# ECU_AutoRC_PWR_SUPPLY_6A_r00.net
KiCad netlist of a schematic drawn in Altium Designer
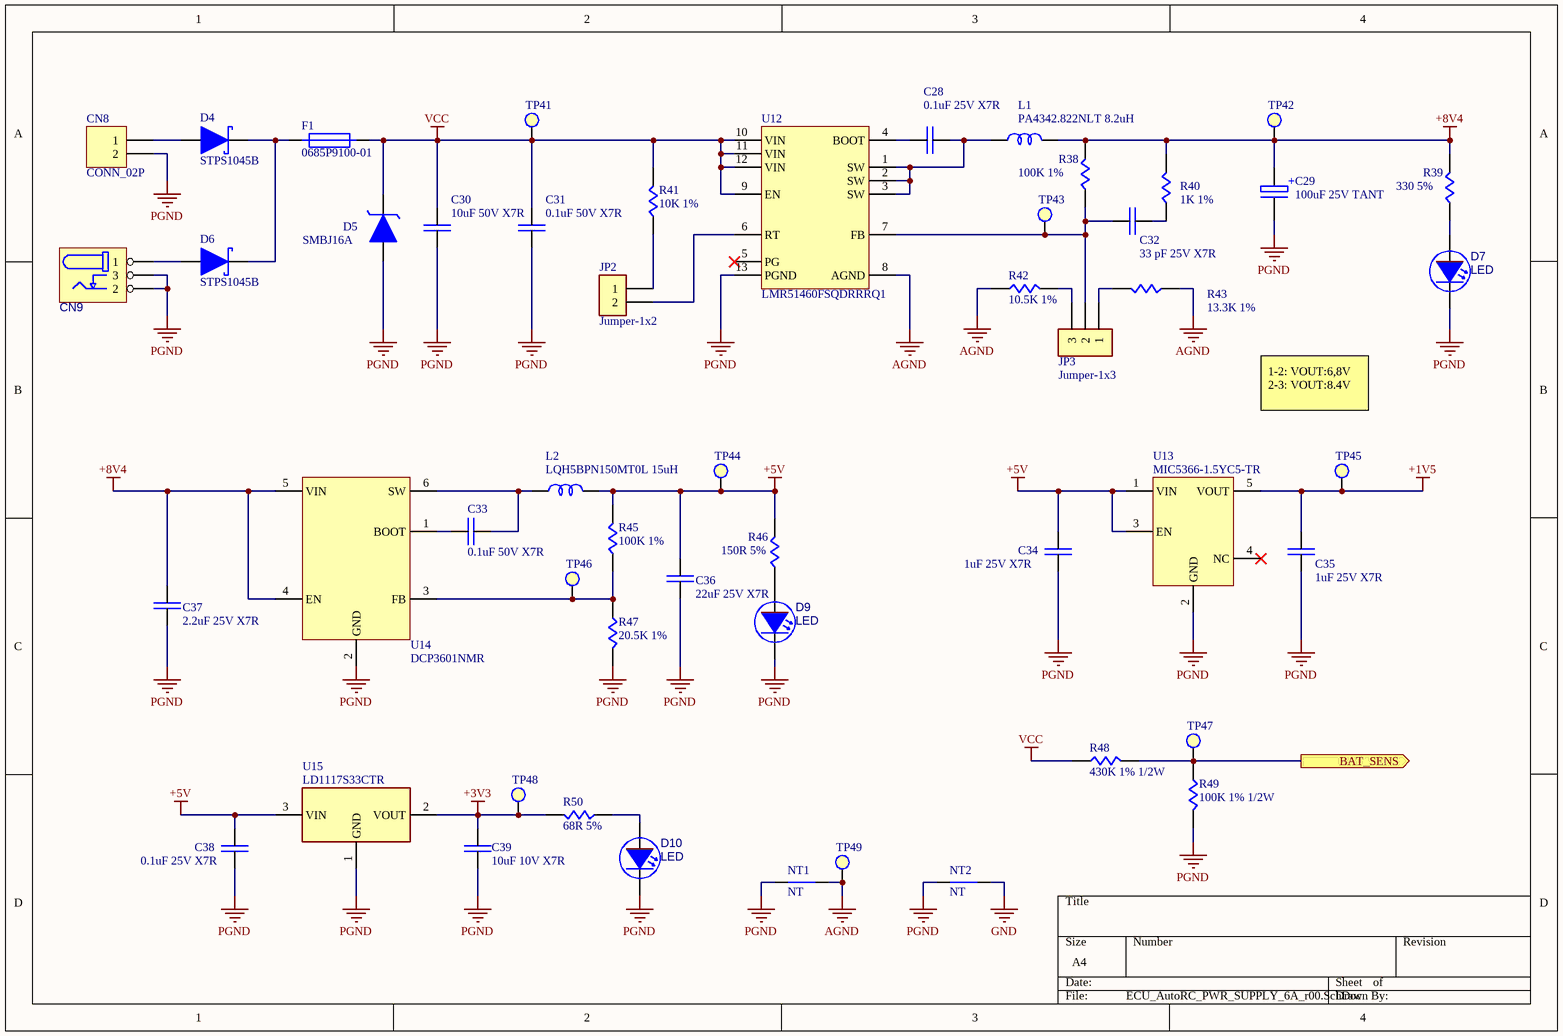
[diagram p0: ECU_AutoRC_PWR_SUPPLY_6A_r00.SchDoc]

(export (version "E")
  (design (tool "Eeschema 10.0.6"))
  (components
    (comp (ref "C28")
      (value "0.1uF 25V X7R")
      (footprint "C_0805")
      (description "Non Polarizated Capacitor")
      (libsource (lib "ECU_AutoRC_r00") (part "Capacitor NP"))
    )
    (comp (ref "C29")
      (value "100uF 25V TANT")
      (footprint "C_TANT_2917")
      (description "Polarizated Capacitor")
      (libsource (lib "ECU_AutoRC_r00") (part "Capacitor Polarizado"))
    )
    (comp (ref "C30")
      (value "10uF 50V X7R")
      (footprint "C_1206")
      (description "Non Polarizated Capacitor")
      (libsource (lib "ECU_AutoRC_r00") (part "Capacitor NP"))
    )
    (comp (ref "C31")
      (value "0.1uF 50V X7R")
      (footprint "C_0805")
      (description "Non Polarizated Capacitor")
      (libsource (lib "ECU_AutoRC_r00") (part "Capacitor NP"))
    )
    (comp (ref "C32")
      (value "33 pF 25V X7R")
      (footprint "C_0805")
      (description "Non Polarizated Capacitor")
      (libsource (lib "ECU_AutoRC_r00") (part "Capacitor NP"))
    )
    (comp (ref "C33")
      (value "0.1uF 50V X7R")
      (footprint "C_0805")
      (description "Non Polarizated Capacitor")
      (libsource (lib "ECU_AutoRC_r00") (part "Capacitor NP"))
    )
    (comp (ref "C34")
      (value "1uF 25V X7R")
      (footprint "C_0805")
      (description "Non Polarizated Capacitor")
      (libsource (lib "ECU_AutoRC_r00") (part "Capacitor NP"))
    )
    (comp (ref "C35")
      (value "1uF 25V X7R")
      (footprint "C_0805")
      (description "Non Polarizated Capacitor")
      (libsource (lib "ECU_AutoRC_r00") (part "Capacitor NP"))
    )
    (comp (ref "C36")
      (value "22uF 25V X7R")
      (footprint "C_0805")
      (description "Non Polarizated Capacitor")
      (libsource (lib "ECU_AutoRC_r00") (part "Capacitor NP"))
    )
    (comp (ref "C37")
      (value "2.2uF 25V X7R")
      (footprint "C_0805")
      (description "Non Polarizated Capacitor")
      (libsource (lib "ECU_AutoRC_r00") (part "Capacitor NP"))
    )
    (comp (ref "C38")
      (value "0.1uF 25V X7R")
      (footprint "C_0805")
      (description "Non Polarizated Capacitor")
      (libsource (lib "ECU_AutoRC_r00") (part "Capacitor NP"))
    )
    (comp (ref "C39")
      (value "10uF 10V X7R")
      (footprint "C_0805")
      (description "Non Polarizated Capacitor")
      (libsource (lib "ECU_AutoRC_r00") (part "Capacitor NP"))
    )
    (comp (ref "CN8")
      (value "CONN_02P")
      (footprint "CONN_BAT")
      (description "2 Pin Connector")
      (libsource (lib "ECU_AutoRC_r00") (part "CONN_02P"))
    )
    (comp (ref "CN9")
      (value "CN_PowerJack")
      (footprint "PJ002B")
      (description "Barrel Power Connector")
      (libsource (lib "ECU_AutoRC_r00") (part "CN_PowerJack"))
    )
    (comp (ref "D4")
      (value "STPS1045B")
      (footprint "TO252_1")
      (description "Diode Schottky")
      (libsource (lib "ECU_AutoRC_r00") (part "Diode_Schottky"))
    )
    (comp (ref "D5")
      (value "SMBJ16A")
      (footprint "D_SMB")
      (description "Diode Zener")
      (libsource (lib "ECU_AutoRC_r00") (part "Diode_Zener"))
    )
    (comp (ref "D6")
      (value "STPS1045B")
      (footprint "TO252_1")
      (description "Diode Schottky")
      (libsource (lib "ECU_AutoRC_r00") (part "Diode_Schottky"))
    )
    (comp (ref "D7") (value "LED") (footprint "LED_0805") (libsource (lib "ECU_AutoRC_r00") (part "LED")))
    (comp (ref "D9") (value "LED") (footprint "LED_0805") (libsource (lib "ECU_AutoRC_r00") (part "LED")))
    (comp (ref "D10") (value "LED") (footprint "LED_0805") (libsource (lib "ECU_AutoRC_r00") (part "LED")))
    (comp (ref "F1")
      (value "0685P9100-01")
      (footprint "F_1206")
      (description "Fuse ¦ Quick Acting")
      (fields (field (name "MF") "Bel Fuse") (field (name "MP") "0679L1000-05"))
      (libsource (lib "ECU_AutoRC_r00") (part "FUSE"))
    )
    (comp (ref "JP2")
      (value "Jumper-1x2")
      (footprint "Header_M_1x2_0.1\"")
      (libsource (lib "ECU_AutoRC_r00") (part "Jumper-1x2"))
    )
    (comp (ref "JP3")
      (value "Jumper-1x3")
      (footprint "Header_M_1x3_0.1\"")
      (libsource (lib "ECU_AutoRC_r00") (part "Jumper-1x3"))
    )
    (comp (ref "L1")
      (value "PA4342.822NLT 8.2uH")
      (footprint "IND_PA4342.822NLT")
      (description "Inductor")
      (libsource (lib "ECU_AutoRC_r00") (part "Inductor"))
    )
    (comp (ref "L2")
      (value "LQH5BPN150MT0L 15uH")
      (footprint "IND_LQH5BPN150MT0L")
      (description "Inductor")
      (libsource (lib "ECU_AutoRC_r00") (part "Inductor"))
    )
    (comp (ref "NT1")
      (value "NT")
      (footprint "NET_TIE")
      (libsource (lib "ECU_AutoRC_r00") (part "NET_TIE_SMD"))
    )
    (comp (ref "NT2")
      (value "NT")
      (footprint "NET_TIE")
      (libsource (lib "ECU_AutoRC_r00") (part "NET_TIE_SMD"))
    )
    (comp (ref "R38")
      (value "100K 1%")
      (footprint "R_0805")
      (description "Resistor")
      (libsource (lib "ECU_AutoRC_r00") (part "Resistor"))
    )
    (comp (ref "R39")
      (value "330 5%")
      (footprint "R_0805")
      (description "Resistor")
      (libsource (lib "ECU_AutoRC_r00") (part "Resistor"))
    )
    (comp (ref "R40")
      (value "1K 1%")
      (footprint "R_0805")
      (description "Resistor")
      (libsource (lib "ECU_AutoRC_r00") (part "Resistor"))
    )
    (comp (ref "R41")
      (value "10K 1%")
      (footprint "R_0805")
      (description "Resistor")
      (libsource (lib "ECU_AutoRC_r00") (part "Resistor"))
    )
    (comp (ref "R42")
      (value "10.5K 1%")
      (footprint "R_0805")
      (description "Resistor")
      (libsource (lib "ECU_AutoRC_r00") (part "Resistor"))
    )
    (comp (ref "R43")
      (value "13.3K 1%")
      (footprint "R_0805")
      (description "Resistor")
      (libsource (lib "ECU_AutoRC_r00") (part "Resistor"))
    )
    (comp (ref "R45")
      (value "100K 1%")
      (footprint "R_0805")
      (description "Resistor")
      (libsource (lib "ECU_AutoRC_r00") (part "Resistor"))
    )
    (comp (ref "R46")
      (value "150R 5%")
      (footprint "R_0805")
      (description "Resistor")
      (libsource (lib "ECU_AutoRC_r00") (part "Resistor"))
    )
    (comp (ref "R47")
      (value "20.5K 1%")
      (footprint "R_0805")
      (description "Resistor")
      (libsource (lib "ECU_AutoRC_r00") (part "Resistor"))
    )
    (comp (ref "R48")
      (value "430K 1% 1/2W")
      (footprint "R_1210")
      (description "Resistor")
      (libsource (lib "ECU_AutoRC_r00") (part "Resistor"))
    )
    (comp (ref "R49")
      (value "100K 1% 1/2W")
      (footprint "R_1210")
      (description "Resistor")
      (libsource (lib "ECU_AutoRC_r00") (part "Resistor"))
    )
    (comp (ref "R50")
      (value "68R 5%")
      (footprint "R_0805")
      (description "Resistor")
      (libsource (lib "ECU_AutoRC_r00") (part "Resistor"))
    )
    (comp (ref "TP41")
      (value "Test Point")
      (footprint "TEST_POINT")
      (libsource (lib "ECU_AutoRC_r00") (part "TestPoint"))
    )
    (comp (ref "TP42")
      (value "Test Point")
      (footprint "TEST_POINT")
      (libsource (lib "ECU_AutoRC_r00") (part "TestPoint"))
    )
    (comp (ref "TP43")
      (value "Test Point")
      (footprint "TEST_POINT")
      (libsource (lib "ECU_AutoRC_r00") (part "TestPoint"))
    )
    (comp (ref "TP44")
      (value "Test Point")
      (footprint "TEST_POINT")
      (libsource (lib "ECU_AutoRC_r00") (part "TestPoint"))
    )
    (comp (ref "TP45")
      (value "Test Point")
      (footprint "TEST_POINT")
      (libsource (lib "ECU_AutoRC_r00") (part "TestPoint"))
    )
    (comp (ref "TP46")
      (value "Test Point")
      (footprint "TEST_POINT")
      (libsource (lib "ECU_AutoRC_r00") (part "TestPoint"))
    )
    (comp (ref "TP47")
      (value "Test Point")
      (footprint "TEST_POINT")
      (libsource (lib "ECU_AutoRC_r00") (part "TestPoint"))
    )
    (comp (ref "TP48")
      (value "Test Point")
      (footprint "TEST_POINT")
      (libsource (lib "ECU_AutoRC_r00") (part "TestPoint"))
    )
    (comp (ref "TP49")
      (value "Test Point")
      (footprint "TEST_POINT")
      (libsource (lib "ECU_AutoRC_r00") (part "TestPoint"))
    )
    (comp (ref "U12")
      (value "LMR51460FSQDRRRQ1")
      (footprint "LMR51460FSQDRRRQ1")
      (description "IC REG BUCK ADJ 6A 12WSON")
      (libsource (lib "ECU_AutoRC_r00") (part "LMR51460FSQDRRRQ1"))
    )
    (comp (ref "U13")
      (value "MIC5366-1.5YC5-TR")
      (footprint "SC 70-5")
      (description "IC REG LINEAR 1.5V 150MA SC-70-5")
      (libsource (lib "ECU_AutoRC_r00") (part "MIC5366-1.5YC5-TR"))
    )
    (comp (ref "U14")
      (value "DCP3601NMR")
      (footprint "SOT23-6")
      (libsource (lib "ECU_AutoRC_r00") (part "DCP3601NMR"))
    )
    (comp (ref "U15")
      (value "LD1117S33CTR")
      (footprint "SOT-223")
      (description "IC REG LINEAR 3.3V 800MA SOT-223")
      (libsource (lib "ECU_AutoRC_r00") (part "LD1117S33CTR"))
    )
  )
  (nets
    (net (code "1") (name "+1V5") (class "Default")
      (node (ref "C35") (pin "1") (pinfunction "1_1") (pintype "passive"))
      (node (ref "TP45") (pin "1") (pintype "passive"))
      (node (ref "U13") (pin "5") (pinfunction "VOUT_5") (pintype "passive"))
    )
    (net (code "2") (name "+3V3") (class "Default")
      (node (ref "C39") (pin "1") (pinfunction "1_1") (pintype "passive"))
      (node (ref "R50") (pin "2") (pinfunction "2_2") (pintype "passive"))
      (node (ref "TP48") (pin "1") (pintype "passive"))
      (node (ref "U15") (pin "2") (pinfunction "VOUT_2") (pintype "passive"))
    )
    (net (code "3") (name "+5V") (class "Default")
      (node (ref "C34") (pin "1") (pinfunction "1_1") (pintype "passive"))
      (node (ref "C36") (pin "1") (pinfunction "1_1") (pintype "passive"))
      (node (ref "C38") (pin "1") (pinfunction "1_1") (pintype "passive"))
      (node (ref "L2") (pin "2") (pinfunction "2_2") (pintype "passive"))
      (node (ref "R45") (pin "2") (pinfunction "2_2") (pintype "passive"))
      (node (ref "R46") (pin "2") (pinfunction "2_2") (pintype "passive"))
      (node (ref "TP44") (pin "1") (pintype "passive"))
      (node (ref "U13") (pin "1") (pinfunction "VIN_1") (pintype "passive"))
      (node (ref "U13") (pin "3") (pinfunction "EN_3") (pintype "passive"))
      (node (ref "U15") (pin "3") (pinfunction "VIN_3") (pintype "passive"))
    )
    (net (code "4") (name "+8V4") (class "Default")
      (node (ref "C29") (pin "1") (pinfunction "1_1") (pintype "passive"))
      (node (ref "C37") (pin "1") (pinfunction "1_1") (pintype "passive"))
      (node (ref "L1") (pin "2") (pinfunction "2_2") (pintype "passive"))
      (node (ref "R38") (pin "2") (pinfunction "2_2") (pintype "passive"))
      (node (ref "R39") (pin "2") (pinfunction "2_2") (pintype "passive"))
      (node (ref "R40") (pin "2") (pinfunction "2_2") (pintype "passive"))
      (node (ref "TP42") (pin "1") (pintype "passive"))
      (node (ref "U14") (pin "4") (pinfunction "EN_4") (pintype "passive"))
      (node (ref "U14") (pin "5") (pinfunction "VIN_5") (pintype "passive"))
    )
    (net (code "5") (name "/BAT_SENS") (class "Default")
      (node (ref "R48") (pin "2") (pinfunction "2_2") (pintype "passive"))
      (node (ref "R49") (pin "1") (pinfunction "1_1") (pintype "passive"))
      (node (ref "TP47") (pin "1") (pintype "passive"))
    )
    (net (code "6") (name "AGND") (class "Default")
      (node (ref "NT1") (pin "2") (pinfunction "2_2") (pintype "passive"))
      (node (ref "R42") (pin "1") (pinfunction "1_1") (pintype "passive"))
      (node (ref "R43") (pin "1") (pinfunction "1_1") (pintype "passive"))
      (node (ref "TP49") (pin "1") (pintype "passive"))
      (node (ref "U12") (pin "8") (pinfunction "AGND_8") (pintype "passive"))
    )
    (net (code "7") (name "GND") (class "Default")
      (node (ref "NT2") (pin "2") (pinfunction "2_2") (pintype "passive"))
    )
    (net (code "8") (name "Net-(C28-Pad2)") (class "Default")
      (node (ref "C28") (pin "2") (pinfunction "2_2") (pintype "passive"))
      (node (ref "L1") (pin "1") (pinfunction "1_1") (pintype "passive"))
      (node (ref "U12") (pin "1") (pinfunction "SW_1") (pintype "passive"))
      (node (ref "U12") (pin "2") (pinfunction "SW_2") (pintype "passive"))
      (node (ref "U12") (pin "3") (pinfunction "SW_3") (pintype "passive"))
    )
    (net (code "9") (name "Net-(C32-Pad2)") (class "Default")
      (node (ref "C32") (pin "2") (pinfunction "2_2") (pintype "passive"))
      (node (ref "R40") (pin "1") (pinfunction "1_1") (pintype "passive"))
    )
    (net (code "10") (name "Net-(D4-Anode)") (class "Default")
      (node (ref "CN8") (pin "1") (pinfunction "1_1") (pintype "passive"))
      (node (ref "D4") (pin "1") (pinfunction "Anode_1") (pintype "passive"))
    )
    (net (code "11") (name "Net-(D4-Catode)") (class "Default")
      (node (ref "D4") (pin "2") (pinfunction "Catode_2") (pintype "passive"))
      (node (ref "D6") (pin "2") (pinfunction "Catode_2") (pintype "passive"))
      (node (ref "F1") (pin "1") (pinfunction "1_1") (pintype "passive"))
    )
    (net (code "12") (name "Net-(D6-Anode)") (class "Default")
      (node (ref "CN9") (pin "1") (pinfunction "1_1") (pintype "passive"))
      (node (ref "D6") (pin "1") (pinfunction "Anode_1") (pintype "passive"))
    )
    (net (code "13") (name "Net-(D7-A)") (class "Default")
      (node (ref "D7") (pin "1") (pinfunction "A_1") (pintype "passive"))
      (node (ref "R39") (pin "1") (pinfunction "1_1") (pintype "passive"))
    )
    (net (code "14") (name "Net-(D9-A)") (class "Default")
      (node (ref "D9") (pin "1") (pinfunction "A_1") (pintype "passive"))
      (node (ref "R46") (pin "1") (pinfunction "1_1") (pintype "passive"))
    )
    (net (code "15") (name "Net-(D10-A)") (class "Default")
      (node (ref "D10") (pin "1") (pinfunction "A_1") (pintype "passive"))
      (node (ref "R50") (pin "1") (pinfunction "1_1") (pintype "passive"))
    )
    (net (code "16") (name "Net-(JP2-Pad1)") (class "Default")
      (node (ref "JP2") (pin "1") (pinfunction "1_1") (pintype "passive"))
      (node (ref "R41") (pin "1") (pinfunction "1_1") (pintype "passive"))
    )
    (net (code "17") (name "Net-(JP3-Pad1)") (class "Default")
      (node (ref "JP3") (pin "1") (pinfunction "1_1") (pintype "passive"))
      (node (ref "R43") (pin "2") (pinfunction "2_2") (pintype "passive"))
    )
    (net (code "18") (name "Net-(JP3-Pad3)") (class "Default")
      (node (ref "JP3") (pin "3") (pinfunction "3_3") (pintype "passive"))
      (node (ref "R42") (pin "2") (pinfunction "2_2") (pintype "passive"))
    )
    (net (code "19") (name "Net-(U12-BOOT)") (class "Default")
      (node (ref "C28") (pin "1") (pinfunction "1_1") (pintype "passive"))
      (node (ref "U12") (pin "4") (pinfunction "BOOT_4") (pintype "passive"))
    )
    (net (code "20") (name "Net-(U12-FB)") (class "Default")
      (node (ref "C32") (pin "1") (pinfunction "1_1") (pintype "passive"))
      (node (ref "JP3") (pin "2") (pinfunction "2_2") (pintype "passive"))
      (node (ref "R38") (pin "1") (pinfunction "1_1") (pintype "passive"))
      (node (ref "TP43") (pin "1") (pintype "passive"))
      (node (ref "U12") (pin "7") (pinfunction "FB_7") (pintype "passive"))
    )
    (net (code "21") (name "Net-(U12-RT)") (class "Default")
      (node (ref "JP2") (pin "2") (pinfunction "2_2") (pintype "passive"))
      (node (ref "U12") (pin "6") (pinfunction "RT_6") (pintype "passive"))
    )
    (net (code "22") (name "Net-(U14-BOOT)") (class "Default")
      (node (ref "C33") (pin "1") (pinfunction "1_1") (pintype "passive"))
      (node (ref "U14") (pin "1") (pinfunction "BOOT_1") (pintype "passive"))
    )
    (net (code "23") (name "Net-(U14-FB)") (class "Default")
      (node (ref "R45") (pin "1") (pinfunction "1_1") (pintype "passive"))
      (node (ref "R47") (pin "1") (pinfunction "1_1") (pintype "passive"))
      (node (ref "TP46") (pin "1") (pintype "passive"))
      (node (ref "U14") (pin "3") (pinfunction "FB_3") (pintype "passive"))
    )
    (net (code "24") (name "Net-(U14-SW)") (class "Default")
      (node (ref "C33") (pin "2") (pinfunction "2_2") (pintype "passive"))
      (node (ref "L2") (pin "1") (pinfunction "1_1") (pintype "passive"))
      (node (ref "U14") (pin "6") (pinfunction "SW_6") (pintype "passive"))
    )
    (net (code "25") (name "PGND") (class "Default")
      (node (ref "C29") (pin "2") (pinfunction "2_2") (pintype "passive"))
      (node (ref "C30") (pin "1") (pinfunction "1_1") (pintype "passive"))
      (node (ref "C31") (pin "1") (pinfunction "1_1") (pintype "passive"))
      (node (ref "C34") (pin "2") (pinfunction "2_2") (pintype "passive"))
      (node (ref "C35") (pin "2") (pinfunction "2_2") (pintype "passive"))
      (node (ref "C36") (pin "2") (pinfunction "2_2") (pintype "passive"))
      (node (ref "C37") (pin "2") (pinfunction "2_2") (pintype "passive"))
      (node (ref "C38") (pin "2") (pinfunction "2_2") (pintype "passive"))
      (node (ref "C39") (pin "2") (pinfunction "2_2") (pintype "passive"))
      (node (ref "CN8") (pin "2") (pinfunction "2_2") (pintype "passive"))
      (node (ref "CN9") (pin "2") (pinfunction "2_2") (pintype "passive"))
      (node (ref "CN9") (pin "3") (pinfunction "3_3") (pintype "passive"))
      (node (ref "D10") (pin "2") (pinfunction "K_2") (pintype "passive"))
      (node (ref "D5") (pin "1") (pinfunction "Anode_1") (pintype "passive"))
      (node (ref "D7") (pin "2") (pinfunction "K_2") (pintype "passive"))
      (node (ref "D9") (pin "2") (pinfunction "K_2") (pintype "passive"))
      (node (ref "NT1") (pin "1") (pinfunction "1_1") (pintype "passive"))
      (node (ref "NT2") (pin "1") (pinfunction "1_1") (pintype "passive"))
      (node (ref "R47") (pin "2") (pinfunction "2_2") (pintype "passive"))
      (node (ref "R49") (pin "2") (pinfunction "2_2") (pintype "passive"))
      (node (ref "U12") (pin "13") (pinfunction "PGND_13") (pintype "passive"))
      (node (ref "U13") (pin "2") (pinfunction "GND_2") (pintype "passive"))
      (node (ref "U14") (pin "2") (pinfunction "GND_2") (pintype "passive"))
      (node (ref "U15") (pin "1") (pinfunction "GND_1") (pintype "passive"))
    )
    (net (code "26") (name "VCC") (class "Default")
      (node (ref "C30") (pin "2") (pinfunction "2_2") (pintype "passive"))
      (node (ref "C31") (pin "2") (pinfunction "2_2") (pintype "passive"))
      (node (ref "D5") (pin "2") (pinfunction "Catode_2") (pintype "passive"))
      (node (ref "F1") (pin "2") (pinfunction "2_2") (pintype "passive"))
      (node (ref "R41") (pin "2") (pinfunction "2_2") (pintype "passive"))
      (node (ref "R48") (pin "1") (pinfunction "1_1") (pintype "passive"))
      (node (ref "TP41") (pin "1") (pintype "passive"))
      (node (ref "U12") (pin "10") (pinfunction "VIN_10") (pintype "passive"))
      (node (ref "U12") (pin "11") (pinfunction "VIN_11") (pintype "passive"))
      (node (ref "U12") (pin "12") (pinfunction "VIN_12") (pintype "passive"))
      (node (ref "U12") (pin "9") (pinfunction "EN_9") (pintype "passive"))
    )
    (net (code "27") (name "unconnected-(U12-PG-Pad5)") (class "Default")
      (node (ref "U12") (pin "5") (pinfunction "PG_5") (pintype "open_emitter+no_connect"))
    )
    (net (code "28") (name "unconnected-(U13-NC-Pad4)") (class "Default")
      (node (ref "U13") (pin "4") (pinfunction "NC_4") (pintype "passive+no_connect"))
    )
  )
)
